# Miasma_fpb_R1_0.net
KiCad netlist of a schematic drawn in EAGLE
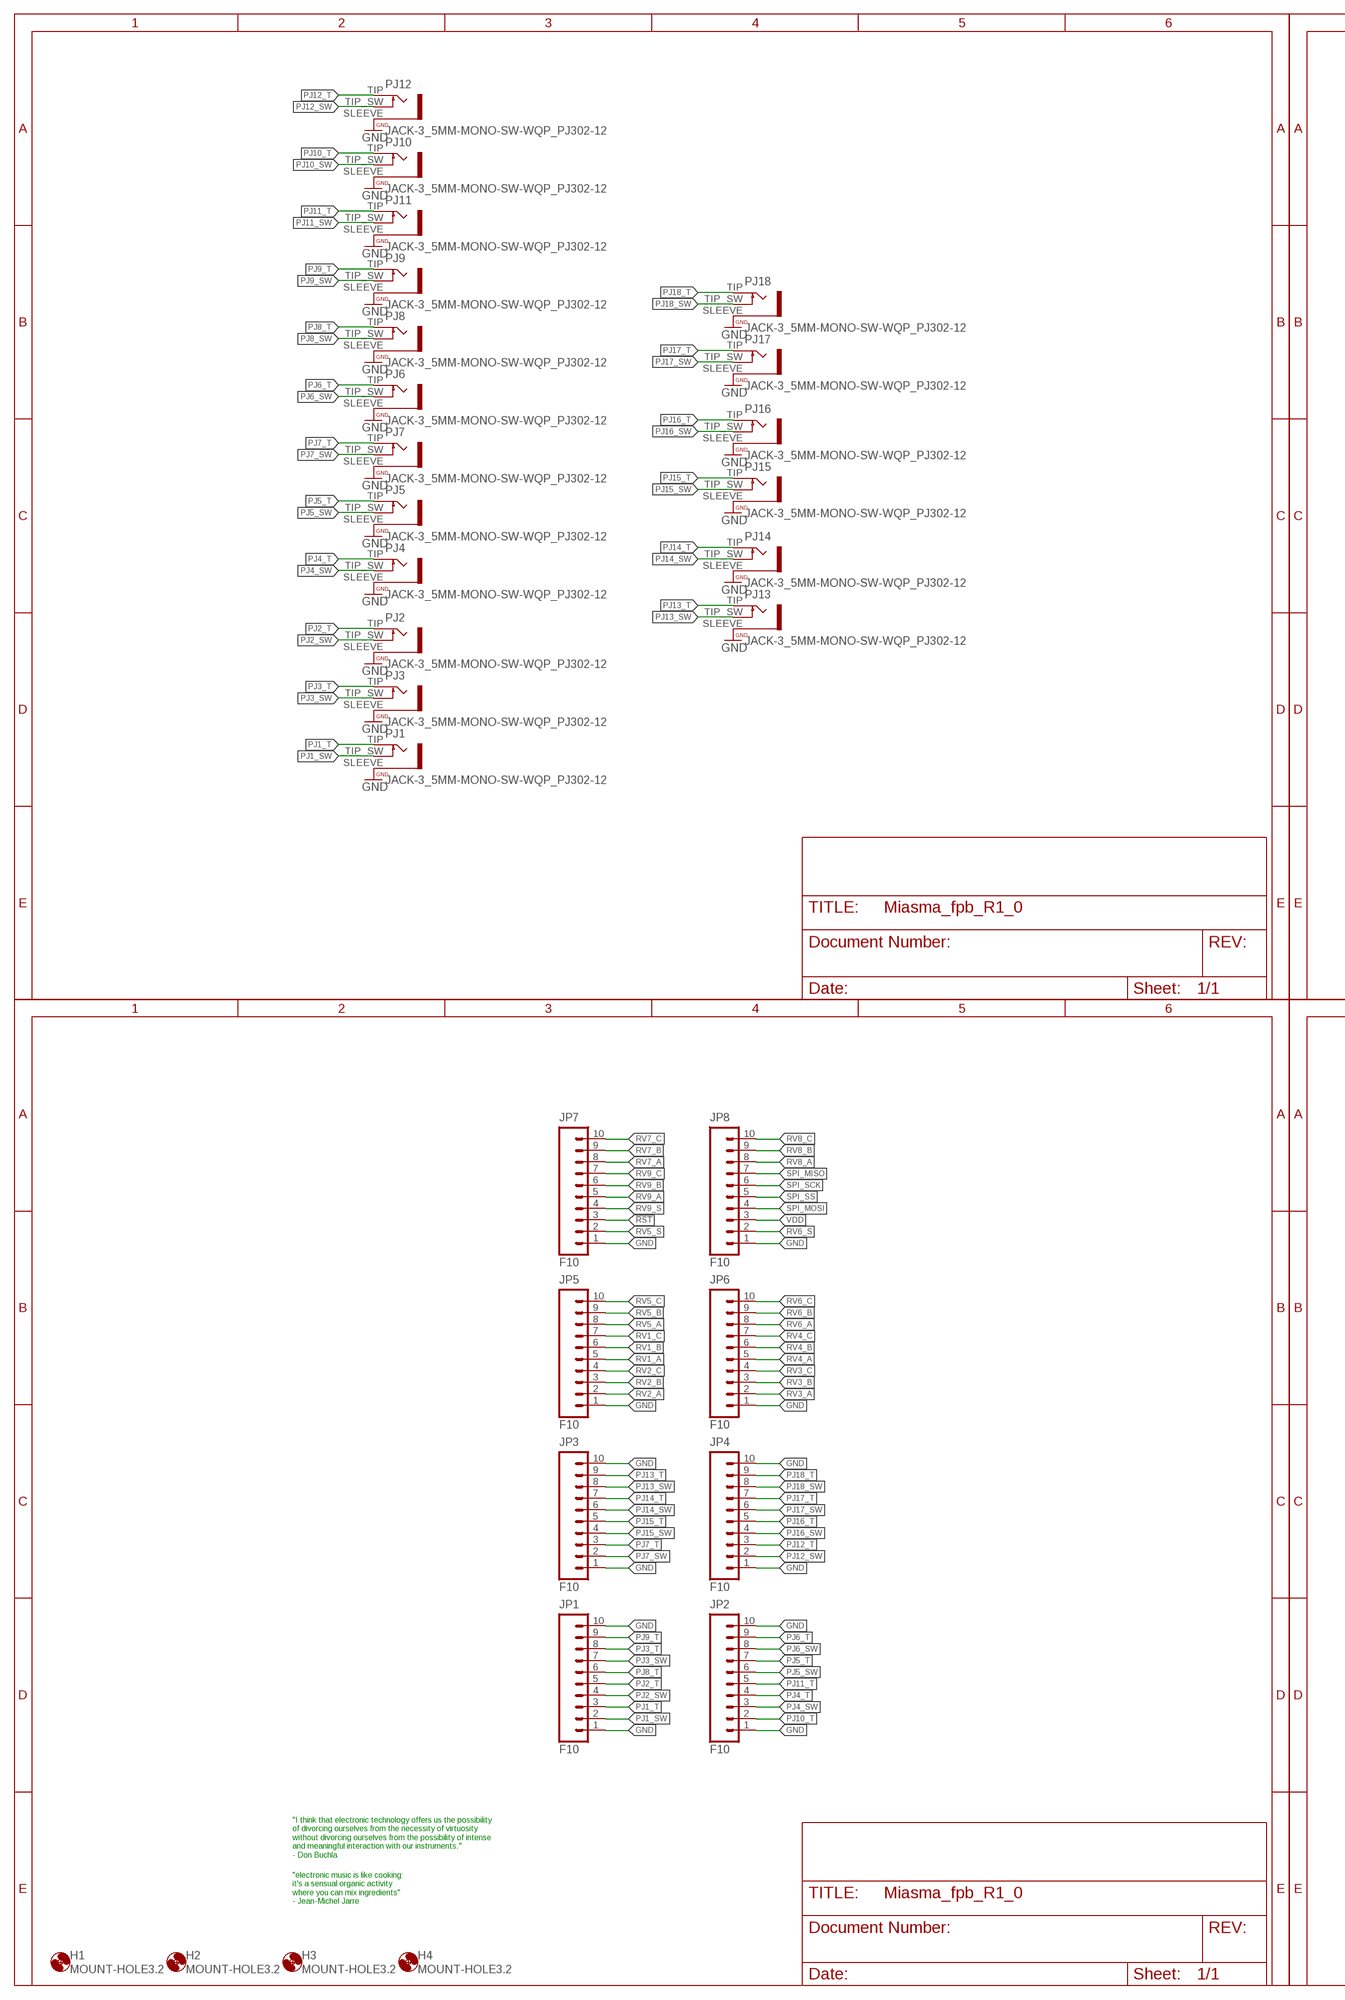
[diagram p0: schematic, sheet 1, part 1 of 2]
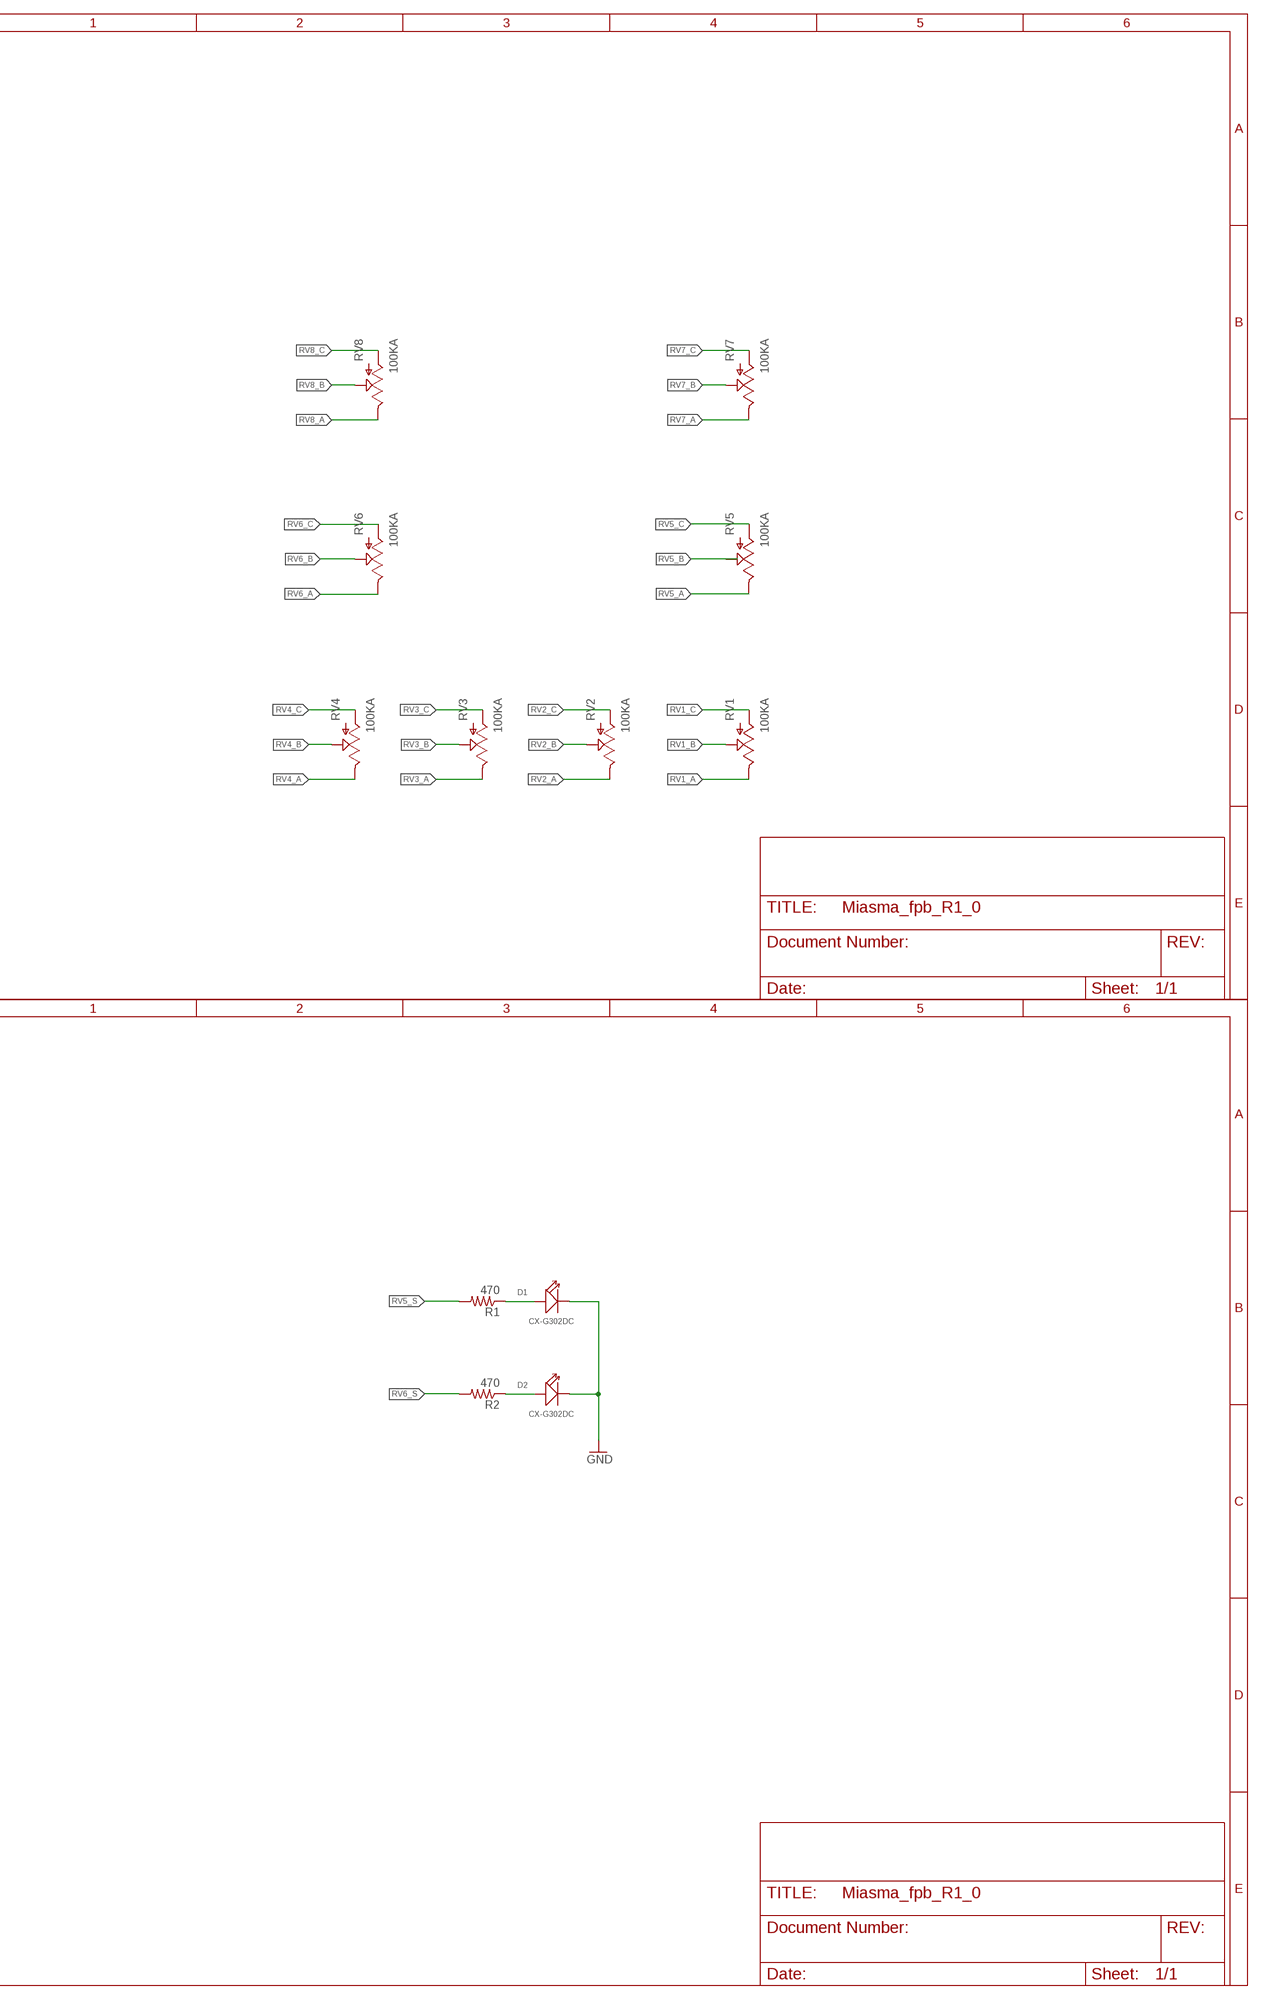
[diagram p1: schematic, sheet 1, part 2 of 2]

(export (version "E")
  (design (tool "Eeschema 10.0.6"))
  (components
    (comp (ref "D1")
      (value "CX-G302DC")
      (footprint "eagle-import:LED2-2.54-D3.0MM")
      (libsource (lib "eagle-import") (part "DIP-LED-GREEN-GREEN(2P-D3MM)"))
    )
    (comp (ref "D2")
      (value "CX-G302DC")
      (footprint "eagle-import:LED2-2.54-D3.0MM")
      (libsource (lib "eagle-import") (part "DIP-LED-GREEN-GREEN(2P-D3MM)"))
    )
    (comp (ref "H1")
      (value "MOUNT-HOLE3.2")
      (footprint "eagle-import:3,2")
      (libsource (lib "eagle-import") (part "MOUNT-HOLE3.2"))
    )
    (comp (ref "H2")
      (value "MOUNT-HOLE3.2")
      (footprint "eagle-import:3,2")
      (libsource (lib "eagle-import") (part "MOUNT-HOLE3.2"))
    )
    (comp (ref "H3")
      (value "MOUNT-HOLE3.2")
      (footprint "eagle-import:3,2")
      (libsource (lib "eagle-import") (part "MOUNT-HOLE3.2"))
    )
    (comp (ref "H4")
      (value "MOUNT-HOLE3.2")
      (footprint "eagle-import:3,2")
      (libsource (lib "eagle-import") (part "MOUNT-HOLE3.2"))
    )
    (comp (ref "JP1")
      (value "F10")
      (footprint "eagle-import:1X10_OCTO")
      (libsource (lib "eagle-import") (part "M10SILK_FEMALE_PTH"))
    )
    (comp (ref "JP2")
      (value "F10")
      (footprint "eagle-import:1X10_OCTO")
      (libsource (lib "eagle-import") (part "M10SILK_FEMALE_PTH"))
    )
    (comp (ref "JP3")
      (value "F10")
      (footprint "eagle-import:1X10_OCTO")
      (libsource (lib "eagle-import") (part "M10SILK_FEMALE_PTH"))
    )
    (comp (ref "JP4")
      (value "F10")
      (footprint "eagle-import:1X10_OCTO")
      (libsource (lib "eagle-import") (part "M10SILK_FEMALE_PTH"))
    )
    (comp (ref "JP5")
      (value "F10")
      (footprint "eagle-import:1X10_OCTO")
      (libsource (lib "eagle-import") (part "M10SILK_FEMALE_PTH"))
    )
    (comp (ref "JP6")
      (value "F10")
      (footprint "eagle-import:1X10_OCTO")
      (libsource (lib "eagle-import") (part "M10SILK_FEMALE_PTH"))
    )
    (comp (ref "JP7")
      (value "F10")
      (footprint "eagle-import:1X10_OCTO")
      (libsource (lib "eagle-import") (part "M10SILK_FEMALE_PTH"))
    )
    (comp (ref "JP8")
      (value "F10")
      (footprint "eagle-import:1X10_OCTO")
      (libsource (lib "eagle-import") (part "M10SILK_FEMALE_PTH"))
    )
    (comp (ref "PJ1")
      (value "JACK-3_5MM-MONO-SW-WQP_PJ302-12")
      (footprint "eagle-import:WQP_PJ301M-12")
      (libsource (lib "eagle-import") (part "JACK-3_5MM-MONO-SW-WQP_PJ302-12"))
    )
    (comp (ref "PJ2")
      (value "JACK-3_5MM-MONO-SW-WQP_PJ302-12")
      (footprint "eagle-import:WQP_PJ301M-12")
      (libsource (lib "eagle-import") (part "JACK-3_5MM-MONO-SW-WQP_PJ302-12"))
    )
    (comp (ref "PJ3")
      (value "JACK-3_5MM-MONO-SW-WQP_PJ302-12")
      (footprint "eagle-import:WQP_PJ301M-12")
      (libsource (lib "eagle-import") (part "JACK-3_5MM-MONO-SW-WQP_PJ302-12"))
    )
    (comp (ref "PJ4")
      (value "JACK-3_5MM-MONO-SW-WQP_PJ302-12")
      (footprint "eagle-import:WQP_PJ301M-12")
      (libsource (lib "eagle-import") (part "JACK-3_5MM-MONO-SW-WQP_PJ302-12"))
    )
    (comp (ref "PJ5")
      (value "JACK-3_5MM-MONO-SW-WQP_PJ302-12")
      (footprint "eagle-import:WQP_PJ301M-12")
      (libsource (lib "eagle-import") (part "JACK-3_5MM-MONO-SW-WQP_PJ302-12"))
    )
    (comp (ref "PJ6")
      (value "JACK-3_5MM-MONO-SW-WQP_PJ302-12")
      (footprint "eagle-import:WQP_PJ301M-12")
      (libsource (lib "eagle-import") (part "JACK-3_5MM-MONO-SW-WQP_PJ302-12"))
    )
    (comp (ref "PJ7")
      (value "JACK-3_5MM-MONO-SW-WQP_PJ302-12")
      (footprint "eagle-import:WQP_PJ301M-12")
      (libsource (lib "eagle-import") (part "JACK-3_5MM-MONO-SW-WQP_PJ302-12"))
    )
    (comp (ref "PJ8")
      (value "JACK-3_5MM-MONO-SW-WQP_PJ302-12")
      (footprint "eagle-import:WQP_PJ301M-12")
      (libsource (lib "eagle-import") (part "JACK-3_5MM-MONO-SW-WQP_PJ302-12"))
    )
    (comp (ref "PJ9")
      (value "JACK-3_5MM-MONO-SW-WQP_PJ302-12")
      (footprint "eagle-import:WQP_PJ301M-12")
      (libsource (lib "eagle-import") (part "JACK-3_5MM-MONO-SW-WQP_PJ302-12"))
    )
    (comp (ref "PJ10")
      (value "JACK-3_5MM-MONO-SW-WQP_PJ302-12")
      (footprint "eagle-import:WQP_PJ301M-12")
      (libsource (lib "eagle-import") (part "JACK-3_5MM-MONO-SW-WQP_PJ302-12"))
    )
    (comp (ref "PJ11")
      (value "JACK-3_5MM-MONO-SW-WQP_PJ302-12")
      (footprint "eagle-import:WQP_PJ301M-12")
      (libsource (lib "eagle-import") (part "JACK-3_5MM-MONO-SW-WQP_PJ302-12"))
    )
    (comp (ref "PJ12")
      (value "JACK-3_5MM-MONO-SW-WQP_PJ302-12")
      (footprint "eagle-import:WQP_PJ301M-12")
      (libsource (lib "eagle-import") (part "JACK-3_5MM-MONO-SW-WQP_PJ302-12"))
    )
    (comp (ref "PJ13")
      (value "JACK-3_5MM-MONO-SW-WQP_PJ302-12")
      (footprint "eagle-import:WQP_PJ301M-12")
      (libsource (lib "eagle-import") (part "JACK-3_5MM-MONO-SW-WQP_PJ302-12"))
    )
    (comp (ref "PJ14")
      (value "JACK-3_5MM-MONO-SW-WQP_PJ302-12")
      (footprint "eagle-import:WQP_PJ301M-12")
      (libsource (lib "eagle-import") (part "JACK-3_5MM-MONO-SW-WQP_PJ302-12"))
    )
    (comp (ref "PJ15")
      (value "JACK-3_5MM-MONO-SW-WQP_PJ302-12")
      (footprint "eagle-import:WQP_PJ301M-12")
      (libsource (lib "eagle-import") (part "JACK-3_5MM-MONO-SW-WQP_PJ302-12"))
    )
    (comp (ref "PJ16")
      (value "JACK-3_5MM-MONO-SW-WQP_PJ302-12")
      (footprint "eagle-import:WQP_PJ301M-12")
      (libsource (lib "eagle-import") (part "JACK-3_5MM-MONO-SW-WQP_PJ302-12"))
    )
    (comp (ref "PJ17")
      (value "JACK-3_5MM-MONO-SW-WQP_PJ302-12")
      (footprint "eagle-import:WQP_PJ301M-12")
      (libsource (lib "eagle-import") (part "JACK-3_5MM-MONO-SW-WQP_PJ302-12"))
    )
    (comp (ref "PJ18")
      (value "JACK-3_5MM-MONO-SW-WQP_PJ302-12")
      (footprint "eagle-import:WQP_PJ301M-12")
      (libsource (lib "eagle-import") (part "JACK-3_5MM-MONO-SW-WQP_PJ302-12"))
    )
    (comp (ref "R1")
      (value "470")
      (footprint "eagle-import:R0603")
      (libsource (lib "eagle-import") (part "R-US_R0603"))
    )
    (comp (ref "R2")
      (value "470")
      (footprint "eagle-import:R0603")
      (libsource (lib "eagle-import") (part "R-US_R0603"))
    )
    (comp (ref "RV1")
      (value "100KA")
      (footprint "eagle-import:ALPS_POT")
      (libsource (lib "eagle-import") (part "POT"))
    )
    (comp (ref "RV2")
      (value "100KA")
      (footprint "eagle-import:ALPS_POT")
      (libsource (lib "eagle-import") (part "POT"))
    )
    (comp (ref "RV3")
      (value "100KA")
      (footprint "eagle-import:ALPS_POT")
      (libsource (lib "eagle-import") (part "POT"))
    )
    (comp (ref "RV4")
      (value "100KA")
      (footprint "eagle-import:ALPS_POT")
      (libsource (lib "eagle-import") (part "POT"))
    )
    (comp (ref "RV5")
      (value "100KA")
      (footprint "eagle-import:ALPS_POT")
      (libsource (lib "eagle-import") (part "POT"))
    )
    (comp (ref "RV6")
      (value "100KA")
      (footprint "eagle-import:ALPS_POT")
      (libsource (lib "eagle-import") (part "POT"))
    )
    (comp (ref "RV7")
      (value "100KA")
      (footprint "eagle-import:ALPS_POT")
      (libsource (lib "eagle-import") (part "POT"))
    )
    (comp (ref "RV8")
      (value "100KA")
      (footprint "eagle-import:ALPS_POT")
      (libsource (lib "eagle-import") (part "POT"))
    )
  )
  (nets
    (net (code "1") (name "/~{RST}") (class "Default")
      (node (ref "JP7") (pin "3") (pinfunction "3_3") (pintype "passive"))
    )
    (net (code "2") (name "GND") (class "Default")
      (node (ref "D1") (pin "K") (pinfunction "-_K") (pintype "passive"))
      (node (ref "D2") (pin "K") (pinfunction "-_K") (pintype "passive"))
      (node (ref "JP1") (pin "1") (pinfunction "1_1") (pintype "passive"))
      (node (ref "JP1") (pin "10") (pinfunction "10_10") (pintype "passive"))
      (node (ref "JP2") (pin "1") (pinfunction "1_1") (pintype "passive"))
      (node (ref "JP2") (pin "10") (pinfunction "10_10") (pintype "passive"))
      (node (ref "JP3") (pin "1") (pinfunction "1_1") (pintype "passive"))
      (node (ref "JP3") (pin "10") (pinfunction "10_10") (pintype "passive"))
      (node (ref "JP4") (pin "1") (pinfunction "1_1") (pintype "passive"))
      (node (ref "JP4") (pin "10") (pinfunction "10_10") (pintype "passive"))
      (node (ref "JP5") (pin "1") (pinfunction "1_1") (pintype "passive"))
      (node (ref "JP6") (pin "1") (pinfunction "1_1") (pintype "passive"))
      (node (ref "JP7") (pin "1") (pinfunction "1_1") (pintype "passive"))
      (node (ref "JP8") (pin "1") (pinfunction "1_1") (pintype "passive"))
      (node (ref "PJ1") (pin "SLEEVE") (pinfunction "SLEEVE_SLEEVE") (pintype "passive"))
      (node (ref "PJ10") (pin "SLEEVE") (pinfunction "SLEEVE_SLEEVE") (pintype "passive"))
      (node (ref "PJ11") (pin "SLEEVE") (pinfunction "SLEEVE_SLEEVE") (pintype "passive"))
      (node (ref "PJ12") (pin "SLEEVE") (pinfunction "SLEEVE_SLEEVE") (pintype "passive"))
      (node (ref "PJ13") (pin "SLEEVE") (pinfunction "SLEEVE_SLEEVE") (pintype "passive"))
      (node (ref "PJ14") (pin "SLEEVE") (pinfunction "SLEEVE_SLEEVE") (pintype "passive"))
      (node (ref "PJ15") (pin "SLEEVE") (pinfunction "SLEEVE_SLEEVE") (pintype "passive"))
      (node (ref "PJ16") (pin "SLEEVE") (pinfunction "SLEEVE_SLEEVE") (pintype "passive"))
      (node (ref "PJ17") (pin "SLEEVE") (pinfunction "SLEEVE_SLEEVE") (pintype "passive"))
      (node (ref "PJ18") (pin "SLEEVE") (pinfunction "SLEEVE_SLEEVE") (pintype "passive"))
      (node (ref "PJ2") (pin "SLEEVE") (pinfunction "SLEEVE_SLEEVE") (pintype "passive"))
      (node (ref "PJ3") (pin "SLEEVE") (pinfunction "SLEEVE_SLEEVE") (pintype "passive"))
      (node (ref "PJ4") (pin "SLEEVE") (pinfunction "SLEEVE_SLEEVE") (pintype "passive"))
      (node (ref "PJ5") (pin "SLEEVE") (pinfunction "SLEEVE_SLEEVE") (pintype "passive"))
      (node (ref "PJ6") (pin "SLEEVE") (pinfunction "SLEEVE_SLEEVE") (pintype "passive"))
      (node (ref "PJ7") (pin "SLEEVE") (pinfunction "SLEEVE_SLEEVE") (pintype "passive"))
      (node (ref "PJ8") (pin "SLEEVE") (pinfunction "SLEEVE_SLEEVE") (pintype "passive"))
      (node (ref "PJ9") (pin "SLEEVE") (pinfunction "SLEEVE_SLEEVE") (pintype "passive"))
    )
    (net (code "3") (name "Net-(D1-+)") (class "Default")
      (node (ref "D1") (pin "A") (pinfunction "+_A") (pintype "passive"))
      (node (ref "R1") (pin "1") (pinfunction "1_1") (pintype "passive"))
    )
    (net (code "4") (name "Net-(D2-+)") (class "Default")
      (node (ref "D2") (pin "A") (pinfunction "+_A") (pintype "passive"))
      (node (ref "R2") (pin "1") (pinfunction "1_1") (pintype "passive"))
    )
    (net (code "5") (name "PJ1_SW") (class "Default")
      (node (ref "JP1") (pin "2") (pinfunction "2_2") (pintype "passive"))
      (node (ref "PJ1") (pin "TIP_SW") (pinfunction "TIP_SW_TIP_SW") (pintype "passive"))
    )
    (net (code "6") (name "PJ1_T") (class "Default")
      (node (ref "JP1") (pin "3") (pinfunction "3_3") (pintype "passive"))
      (node (ref "PJ1") (pin "TIP") (pinfunction "TIP_TIP") (pintype "passive"))
    )
    (net (code "7") (name "PJ2_SW") (class "Default")
      (node (ref "JP1") (pin "4") (pinfunction "4_4") (pintype "passive"))
      (node (ref "PJ2") (pin "TIP_SW") (pinfunction "TIP_SW_TIP_SW") (pintype "passive"))
    )
    (net (code "8") (name "PJ2_T") (class "Default")
      (node (ref "JP1") (pin "5") (pinfunction "5_5") (pintype "passive"))
      (node (ref "PJ2") (pin "TIP") (pinfunction "TIP_TIP") (pintype "passive"))
    )
    (net (code "9") (name "PJ3_SW") (class "Default")
      (node (ref "JP1") (pin "7") (pinfunction "7_7") (pintype "passive"))
      (node (ref "PJ3") (pin "TIP_SW") (pinfunction "TIP_SW_TIP_SW") (pintype "passive"))
    )
    (net (code "10") (name "PJ3_T") (class "Default")
      (node (ref "JP1") (pin "8") (pinfunction "8_8") (pintype "passive"))
      (node (ref "PJ3") (pin "TIP") (pinfunction "TIP_TIP") (pintype "passive"))
    )
    (net (code "11") (name "PJ4_SW") (class "Default")
      (node (ref "JP2") (pin "3") (pinfunction "3_3") (pintype "passive"))
      (node (ref "PJ4") (pin "TIP_SW") (pinfunction "TIP_SW_TIP_SW") (pintype "passive"))
    )
    (net (code "12") (name "PJ4_T") (class "Default")
      (node (ref "JP2") (pin "4") (pinfunction "4_4") (pintype "passive"))
      (node (ref "PJ4") (pin "TIP") (pinfunction "TIP_TIP") (pintype "passive"))
    )
    (net (code "13") (name "PJ5_SW") (class "Default")
      (node (ref "JP2") (pin "6") (pinfunction "6_6") (pintype "passive"))
      (node (ref "PJ5") (pin "TIP_SW") (pinfunction "TIP_SW_TIP_SW") (pintype "passive"))
    )
    (net (code "14") (name "PJ5_T") (class "Default")
      (node (ref "JP2") (pin "7") (pinfunction "7_7") (pintype "passive"))
      (node (ref "PJ5") (pin "TIP") (pinfunction "TIP_TIP") (pintype "passive"))
    )
    (net (code "15") (name "PJ6_SW") (class "Default")
      (node (ref "JP2") (pin "8") (pinfunction "8_8") (pintype "passive"))
      (node (ref "PJ6") (pin "TIP_SW") (pinfunction "TIP_SW_TIP_SW") (pintype "passive"))
    )
    (net (code "16") (name "PJ6_T") (class "Default")
      (node (ref "JP2") (pin "9") (pinfunction "9_9") (pintype "passive"))
      (node (ref "PJ6") (pin "TIP") (pinfunction "TIP_TIP") (pintype "passive"))
    )
    (net (code "17") (name "PJ7_SW") (class "Default")
      (node (ref "JP3") (pin "2") (pinfunction "2_2") (pintype "passive"))
      (node (ref "PJ7") (pin "TIP_SW") (pinfunction "TIP_SW_TIP_SW") (pintype "passive"))
    )
    (net (code "18") (name "PJ7_T") (class "Default")
      (node (ref "JP3") (pin "3") (pinfunction "3_3") (pintype "passive"))
      (node (ref "PJ7") (pin "TIP") (pinfunction "TIP_TIP") (pintype "passive"))
    )
    (net (code "19") (name "PJ8_SW") (class "Default")
      (node (ref "PJ8") (pin "TIP_SW") (pinfunction "TIP_SW_TIP_SW") (pintype "passive"))
    )
    (net (code "20") (name "PJ8_T") (class "Default")
      (node (ref "JP1") (pin "6") (pinfunction "6_6") (pintype "passive"))
      (node (ref "PJ8") (pin "TIP") (pinfunction "TIP_TIP") (pintype "passive"))
    )
    (net (code "21") (name "PJ9_SW") (class "Default")
      (node (ref "PJ9") (pin "TIP_SW") (pinfunction "TIP_SW_TIP_SW") (pintype "passive"))
    )
    (net (code "22") (name "PJ9_T") (class "Default")
      (node (ref "JP1") (pin "9") (pinfunction "9_9") (pintype "passive"))
      (node (ref "PJ9") (pin "TIP") (pinfunction "TIP_TIP") (pintype "passive"))
    )
    (net (code "23") (name "PJ10_SW") (class "Default")
      (node (ref "PJ10") (pin "TIP_SW") (pinfunction "TIP_SW_TIP_SW") (pintype "passive"))
    )
    (net (code "24") (name "PJ10_T") (class "Default")
      (node (ref "JP2") (pin "2") (pinfunction "2_2") (pintype "passive"))
      (node (ref "PJ10") (pin "TIP") (pinfunction "TIP_TIP") (pintype "passive"))
    )
    (net (code "25") (name "PJ11_SW") (class "Default")
      (node (ref "PJ11") (pin "TIP_SW") (pinfunction "TIP_SW_TIP_SW") (pintype "passive"))
    )
    (net (code "26") (name "PJ11_T") (class "Default")
      (node (ref "JP2") (pin "5") (pinfunction "5_5") (pintype "passive"))
      (node (ref "PJ11") (pin "TIP") (pinfunction "TIP_TIP") (pintype "passive"))
    )
    (net (code "27") (name "PJ12_SW") (class "Default")
      (node (ref "JP4") (pin "2") (pinfunction "2_2") (pintype "passive"))
      (node (ref "PJ12") (pin "TIP_SW") (pinfunction "TIP_SW_TIP_SW") (pintype "passive"))
    )
    (net (code "28") (name "PJ12_T") (class "Default")
      (node (ref "JP4") (pin "3") (pinfunction "3_3") (pintype "passive"))
      (node (ref "PJ12") (pin "TIP") (pinfunction "TIP_TIP") (pintype "passive"))
    )
    (net (code "29") (name "PJ13_SW") (class "Default")
      (node (ref "JP3") (pin "8") (pinfunction "8_8") (pintype "passive"))
      (node (ref "PJ13") (pin "TIP_SW") (pinfunction "TIP_SW_TIP_SW") (pintype "passive"))
    )
    (net (code "30") (name "PJ13_T") (class "Default")
      (node (ref "JP3") (pin "9") (pinfunction "9_9") (pintype "passive"))
      (node (ref "PJ13") (pin "TIP") (pinfunction "TIP_TIP") (pintype "passive"))
    )
    (net (code "31") (name "PJ14_SW") (class "Default")
      (node (ref "JP3") (pin "6") (pinfunction "6_6") (pintype "passive"))
      (node (ref "PJ14") (pin "TIP_SW") (pinfunction "TIP_SW_TIP_SW") (pintype "passive"))
    )
    (net (code "32") (name "PJ14_T") (class "Default")
      (node (ref "JP3") (pin "7") (pinfunction "7_7") (pintype "passive"))
      (node (ref "PJ14") (pin "TIP") (pinfunction "TIP_TIP") (pintype "passive"))
    )
    (net (code "33") (name "PJ15_SW") (class "Default")
      (node (ref "JP3") (pin "4") (pinfunction "4_4") (pintype "passive"))
      (node (ref "PJ15") (pin "TIP_SW") (pinfunction "TIP_SW_TIP_SW") (pintype "passive"))
    )
    (net (code "34") (name "PJ15_T") (class "Default")
      (node (ref "JP3") (pin "5") (pinfunction "5_5") (pintype "passive"))
      (node (ref "PJ15") (pin "TIP") (pinfunction "TIP_TIP") (pintype "passive"))
    )
    (net (code "35") (name "PJ16_SW") (class "Default")
      (node (ref "JP4") (pin "4") (pinfunction "4_4") (pintype "passive"))
      (node (ref "PJ16") (pin "TIP_SW") (pinfunction "TIP_SW_TIP_SW") (pintype "passive"))
    )
    (net (code "36") (name "PJ16_T") (class "Default")
      (node (ref "JP4") (pin "5") (pinfunction "5_5") (pintype "passive"))
      (node (ref "PJ16") (pin "TIP") (pinfunction "TIP_TIP") (pintype "passive"))
    )
    (net (code "37") (name "PJ17_SW") (class "Default")
      (node (ref "JP4") (pin "6") (pinfunction "6_6") (pintype "passive"))
      (node (ref "PJ17") (pin "TIP_SW") (pinfunction "TIP_SW_TIP_SW") (pintype "passive"))
    )
    (net (code "38") (name "PJ17_T") (class "Default")
      (node (ref "JP4") (pin "7") (pinfunction "7_7") (pintype "passive"))
      (node (ref "PJ17") (pin "TIP") (pinfunction "TIP_TIP") (pintype "passive"))
    )
    (net (code "39") (name "PJ18_SW") (class "Default")
      (node (ref "JP4") (pin "8") (pinfunction "8_8") (pintype "passive"))
      (node (ref "PJ18") (pin "TIP_SW") (pinfunction "TIP_SW_TIP_SW") (pintype "passive"))
    )
    (net (code "40") (name "PJ18_T") (class "Default")
      (node (ref "JP4") (pin "9") (pinfunction "9_9") (pintype "passive"))
      (node (ref "PJ18") (pin "TIP") (pinfunction "TIP_TIP") (pintype "passive"))
    )
    (net (code "41") (name "RV1_A") (class "Default")
      (node (ref "JP5") (pin "5") (pinfunction "5_5") (pintype "passive"))
      (node (ref "RV1") (pin "P$1") (pinfunction "3_P$1") (pintype "passive"))
    )
    (net (code "42") (name "RV1_B") (class "Default")
      (node (ref "JP5") (pin "6") (pinfunction "6_6") (pintype "passive"))
      (node (ref "RV1") (pin "P$2") (pinfunction "2_P$2") (pintype "passive"))
    )
    (net (code "43") (name "RV1_C") (class "Default")
      (node (ref "JP5") (pin "7") (pinfunction "7_7") (pintype "passive"))
      (node (ref "RV1") (pin "P$3") (pinfunction "1_P$3") (pintype "passive"))
    )
    (net (code "44") (name "RV2_A") (class "Default")
      (node (ref "JP5") (pin "2") (pinfunction "2_2") (pintype "passive"))
      (node (ref "RV2") (pin "P$1") (pinfunction "3_P$1") (pintype "passive"))
    )
    (net (code "45") (name "RV2_B") (class "Default")
      (node (ref "JP5") (pin "3") (pinfunction "3_3") (pintype "passive"))
      (node (ref "RV2") (pin "P$2") (pinfunction "2_P$2") (pintype "passive"))
    )
    (net (code "46") (name "RV2_C") (class "Default")
      (node (ref "JP5") (pin "4") (pinfunction "4_4") (pintype "passive"))
      (node (ref "RV2") (pin "P$3") (pinfunction "1_P$3") (pintype "passive"))
    )
    (net (code "47") (name "RV3_A") (class "Default")
      (node (ref "JP6") (pin "2") (pinfunction "2_2") (pintype "passive"))
      (node (ref "RV3") (pin "P$1") (pinfunction "3_P$1") (pintype "passive"))
    )
    (net (code "48") (name "RV3_B") (class "Default")
      (node (ref "JP6") (pin "3") (pinfunction "3_3") (pintype "passive"))
      (node (ref "RV3") (pin "P$2") (pinfunction "2_P$2") (pintype "passive"))
    )
    (net (code "49") (name "RV3_C") (class "Default")
      (node (ref "JP6") (pin "4") (pinfunction "4_4") (pintype "passive"))
      (node (ref "RV3") (pin "P$3") (pinfunction "1_P$3") (pintype "passive"))
    )
    (net (code "50") (name "RV4_A") (class "Default")
      (node (ref "JP6") (pin "5") (pinfunction "5_5") (pintype "passive"))
      (node (ref "RV4") (pin "P$1") (pinfunction "3_P$1") (pintype "passive"))
    )
    (net (code "51") (name "RV4_B") (class "Default")
      (node (ref "JP6") (pin "6") (pinfunction "6_6") (pintype "passive"))
      (node (ref "RV4") (pin "P$2") (pinfunction "2_P$2") (pintype "passive"))
    )
    (net (code "52") (name "RV4_C") (class "Default")
      (node (ref "JP6") (pin "7") (pinfunction "7_7") (pintype "passive"))
      (node (ref "RV4") (pin "P$3") (pinfunction "1_P$3") (pintype "passive"))
    )
    (net (code "53") (name "RV5_A") (class "Default")
      (node (ref "JP5") (pin "8") (pinfunction "8_8") (pintype "passive"))
      (node (ref "RV5") (pin "P$1") (pinfunction "3_P$1") (pintype "passive"))
    )
    (net (code "54") (name "RV5_B") (class "Default")
      (node (ref "JP5") (pin "9") (pinfunction "9_9") (pintype "passive"))
      (node (ref "RV5") (pin "P$2") (pinfunction "2_P$2") (pintype "passive"))
    )
    (net (code "55") (name "RV5_C") (class "Default")
      (node (ref "JP5") (pin "10") (pinfunction "10_10") (pintype "passive"))
      (node (ref "RV5") (pin "P$3") (pinfunction "1_P$3") (pintype "passive"))
    )
    (net (code "56") (name "RV5_S") (class "Default")
      (node (ref "JP7") (pin "2") (pinfunction "2_2") (pintype "passive"))
      (node (ref "R1") (pin "2") (pinfunction "2_2") (pintype "passive"))
    )
    (net (code "57") (name "RV6_A") (class "Default")
      (node (ref "JP6") (pin "8") (pinfunction "8_8") (pintype "passive"))
      (node (ref "RV6") (pin "P$1") (pinfunction "3_P$1") (pintype "passive"))
    )
    (net (code "58") (name "RV6_B") (class "Default")
      (node (ref "JP6") (pin "9") (pinfunction "9_9") (pintype "passive"))
      (node (ref "RV6") (pin "P$2") (pinfunction "2_P$2") (pintype "passive"))
    )
    (net (code "59") (name "RV6_C") (class "Default")
      (node (ref "JP6") (pin "10") (pinfunction "10_10") (pintype "passive"))
      (node (ref "RV6") (pin "P$3") (pinfunction "1_P$3") (pintype "passive"))
    )
    (net (code "60") (name "RV6_S") (class "Default")
      (node (ref "JP8") (pin "2") (pinfunction "2_2") (pintype "passive"))
      (node (ref "R2") (pin "2") (pinfunction "2_2") (pintype "passive"))
    )
    (net (code "61") (name "RV7_A") (class "Default")
      (node (ref "JP7") (pin "8") (pinfunction "8_8") (pintype "passive"))
      (node (ref "RV7") (pin "P$1") (pinfunction "3_P$1") (pintype "passive"))
    )
    (net (code "62") (name "RV7_B") (class "Default")
      (node (ref "JP7") (pin "9") (pinfunction "9_9") (pintype "passive"))
      (node (ref "RV7") (pin "P$2") (pinfunction "2_P$2") (pintype "passive"))
    )
    (net (code "63") (name "RV7_C") (class "Default")
      (node (ref "JP7") (pin "10") (pinfunction "10_10") (pintype "passive"))
      (node (ref "RV7") (pin "P$3") (pinfunction "1_P$3") (pintype "passive"))
    )
    (net (code "64") (name "RV8_A") (class "Default")
      (node (ref "JP8") (pin "8") (pinfunction "8_8") (pintype "passive"))
      (node (ref "RV8") (pin "P$1") (pinfunction "3_P$1") (pintype "passive"))
    )
    (net (code "65") (name "RV8_B") (class "Default")
      (node (ref "JP8") (pin "9") (pinfunction "9_9") (pintype "passive"))
      (node (ref "RV8") (pin "P$2") (pinfunction "2_P$2") (pintype "passive"))
    )
    (net (code "66") (name "RV8_C") (class "Default")
      (node (ref "JP8") (pin "10") (pinfunction "10_10") (pintype "passive"))
      (node (ref "RV8") (pin "P$3") (pinfunction "1_P$3") (pintype "passive"))
    )
    (net (code "67") (name "RV9_A") (class "Default")
      (node (ref "JP7") (pin "5") (pinfunction "5_5") (pintype "passive"))
    )
    (net (code "68") (name "RV9_B") (class "Default")
      (node (ref "JP7") (pin "6") (pinfunction "6_6") (pintype "passive"))
    )
    (net (code "69") (name "RV9_C") (class "Default")
      (node (ref "JP7") (pin "7") (pinfunction "7_7") (pintype "passive"))
    )
    (net (code "70") (name "RV9_S") (class "Default")
      (node (ref "JP7") (pin "4") (pinfunction "4_4") (pintype "passive"))
    )
    (net (code "71") (name "SPI_MISO") (class "Default")
      (node (ref "JP8") (pin "7") (pinfunction "7_7") (pintype "passive"))
    )
    (net (code "72") (name "SPI_MOSI") (class "Default")
      (node (ref "JP8") (pin "4") (pinfunction "4_4") (pintype "passive"))
    )
    (net (code "73") (name "SPI_SCK") (class "Default")
      (node (ref "JP8") (pin "6") (pinfunction "6_6") (pintype "passive"))
    )
    (net (code "74") (name "SPI_SS") (class "Default")
      (node (ref "JP8") (pin "5") (pinfunction "5_5") (pintype "passive"))
    )
    (net (code "75") (name "VDD") (class "Default")
      (node (ref "JP8") (pin "3") (pinfunction "3_3") (pintype "passive"))
    )
  )
)
